# CTRL_LOGIC.net
KiCad netlist of a schematic drawn in Altium Designer
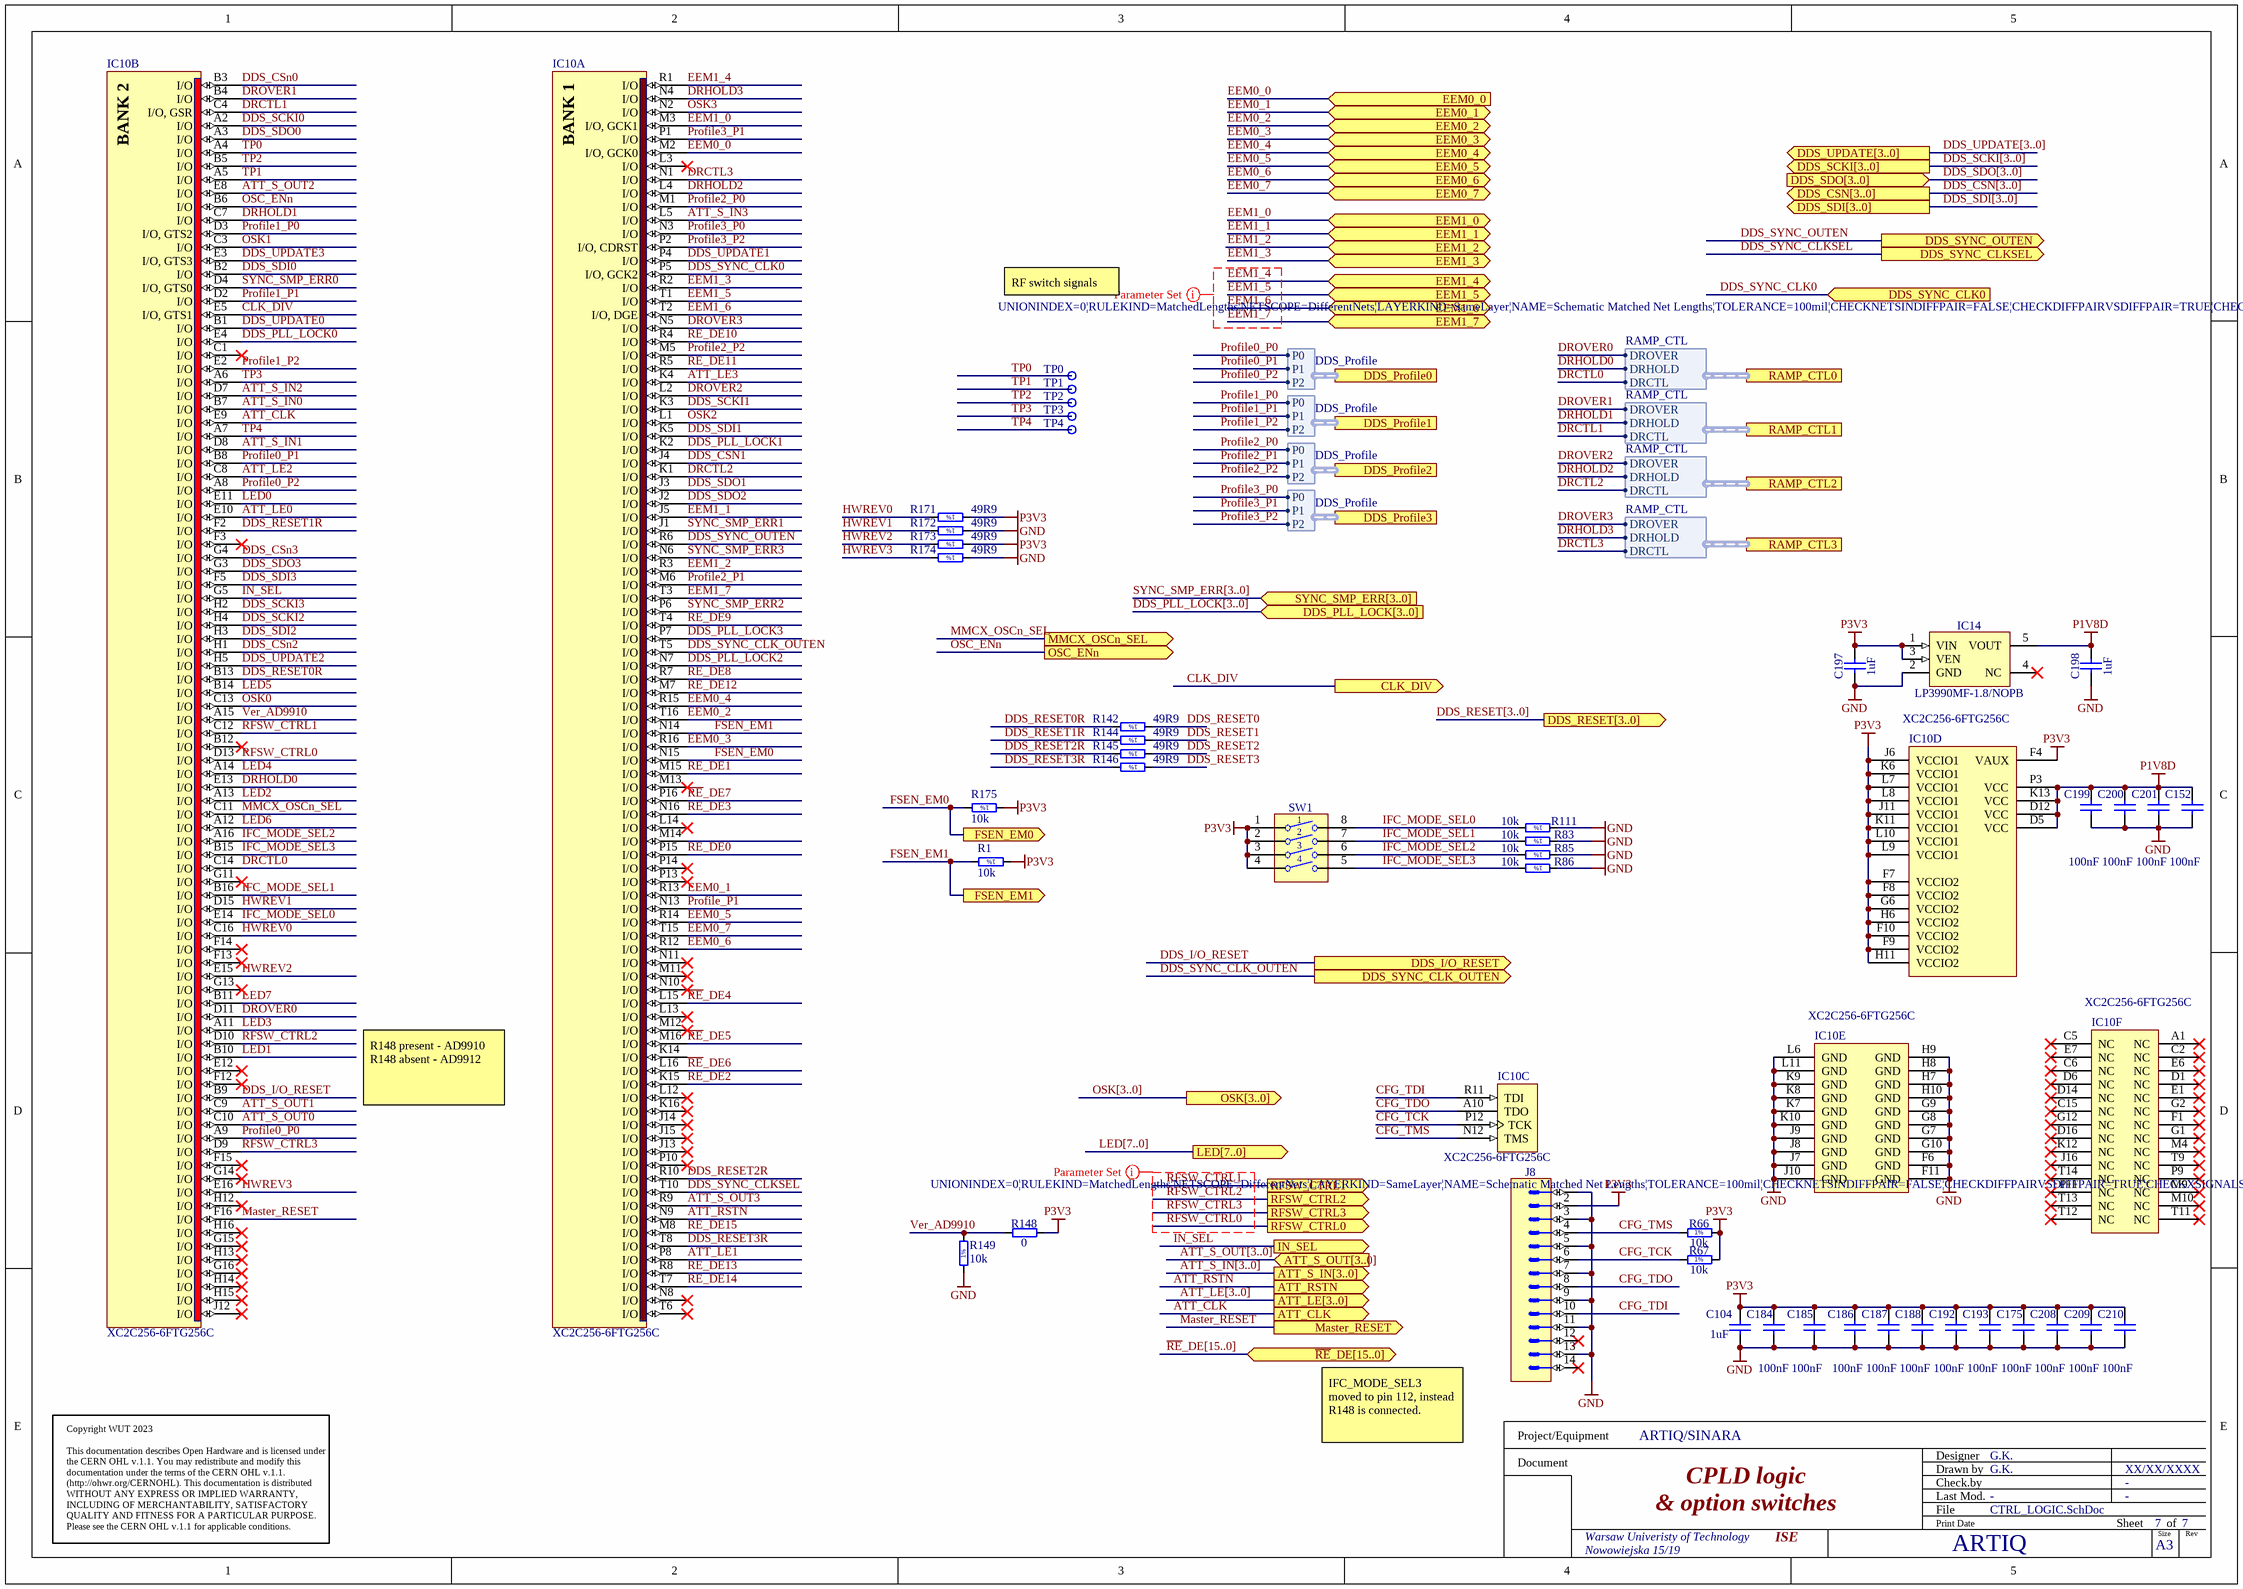
[diagram p0: CTRL_LOGIC.SchDoc]

(export (version "E")
  (design (tool "Eeschema 10.0.6"))
  (components
    (comp (ref "C104")
      (value "1uF")
      (footprint "CAPC1005X55N")
      (description "Non-polarised capacitor")
      (fields
        (field (name "PART NUMBER") "CC0402_1UF_16V_10%_X5R")
        (field (name "VOLTAGE") "16V")
        (field (name "AUTHOR") "CERN DEM JLC")
      )
      (libsource (lib "Capacitors") (part "Capacitor - non polarized"))
    )
    (comp (ref "C152")
      (value "100nF")
      (footprint "CAPC1005X55N")
      (description "Non-polarised capacitor")
      (fields
        (field (name "PART NUMBER") "CC0402_100NF_16V_10%_X5R")
        (field (name "VOLTAGE") "16V")
        (field (name "AUTHOR") "CERN DEM JLC")
      )
      (libsource (lib "Capacitors") (part "Capacitor - non polarized"))
    )
    (comp (ref "C175")
      (value "100nF")
      (footprint "CAPC1005X55N")
      (description "Non-polarised capacitor")
      (fields
        (field (name "PART NUMBER") "CC0402_100NF_16V_10%_X5R")
        (field (name "VOLTAGE") "16V")
        (field (name "AUTHOR") "CERN DEM JLC")
      )
      (libsource (lib "Capacitors") (part "Capacitor - non polarized"))
    )
    (comp (ref "C184")
      (value "100nF")
      (footprint "CAPC1005X55N")
      (description "Non-polarised capacitor")
      (fields
        (field (name "PART NUMBER") "CC0402_100NF_16V_10%_X5R")
        (field (name "VOLTAGE") "16V")
        (field (name "AUTHOR") "CERN DEM JLC")
      )
      (libsource (lib "Capacitors") (part "Capacitor - non polarized"))
    )
    (comp (ref "C185")
      (value "100nF")
      (footprint "CAPC1005X55N")
      (description "Non-polarised capacitor")
      (fields
        (field (name "PART NUMBER") "CC0402_100NF_16V_10%_X5R")
        (field (name "VOLTAGE") "16V")
        (field (name "AUTHOR") "CERN DEM JLC")
      )
      (libsource (lib "Capacitors") (part "Capacitor - non polarized"))
    )
    (comp (ref "C186")
      (value "100nF")
      (footprint "CAPC1005X55N")
      (description "Non-polarised capacitor")
      (fields
        (field (name "PART NUMBER") "CC0402_100NF_16V_10%_X5R")
        (field (name "VOLTAGE") "16V")
        (field (name "AUTHOR") "CERN DEM JLC")
      )
      (libsource (lib "Capacitors") (part "Capacitor - non polarized"))
    )
    (comp (ref "C187")
      (value "100nF")
      (footprint "CAPC1005X55N")
      (description "Non-polarised capacitor")
      (fields
        (field (name "PART NUMBER") "CC0402_100NF_16V_10%_X5R")
        (field (name "VOLTAGE") "16V")
        (field (name "AUTHOR") "CERN DEM JLC")
      )
      (libsource (lib "Capacitors") (part "Capacitor - non polarized"))
    )
    (comp (ref "C188")
      (value "100nF")
      (footprint "CAPC1005X55N")
      (description "Non-polarised capacitor")
      (fields
        (field (name "PART NUMBER") "CC0402_100NF_16V_10%_X5R")
        (field (name "VOLTAGE") "16V")
        (field (name "AUTHOR") "CERN DEM JLC")
      )
      (libsource (lib "Capacitors") (part "Capacitor - non polarized"))
    )
    (comp (ref "C192")
      (value "100nF")
      (footprint "CAPC1005X55N")
      (description "Non-polarised capacitor")
      (fields
        (field (name "PART NUMBER") "CC0402_100NF_16V_10%_X5R")
        (field (name "VOLTAGE") "16V")
        (field (name "AUTHOR") "CERN DEM JLC")
      )
      (libsource (lib "Capacitors") (part "Capacitor - non polarized"))
    )
    (comp (ref "C193")
      (value "100nF")
      (footprint "CAPC1005X55N")
      (description "Non-polarised capacitor")
      (fields
        (field (name "PART NUMBER") "CC0402_100NF_16V_10%_X5R")
        (field (name "VOLTAGE") "16V")
        (field (name "AUTHOR") "CERN DEM JLC")
      )
      (libsource (lib "Capacitors") (part "Capacitor - non polarized"))
    )
    (comp (ref "C197")
      (value "1uF")
      (footprint "CAPC1005X55N")
      (description "Non-polarised capacitor")
      (fields
        (field (name "PART NUMBER") "CC0402_1UF_16V_10%_X5R")
        (field (name "VOLTAGE") "16V")
        (field (name "AUTHOR") "CERN DEM JLC")
      )
      (libsource (lib "Capacitors") (part "Capacitor - non polarized"))
    )
    (comp (ref "C198")
      (value "1uF")
      (footprint "CAPC1005X55N")
      (description "Non-polarised capacitor")
      (fields
        (field (name "PART NUMBER") "CC0402_1UF_16V_10%_X5R")
        (field (name "VOLTAGE") "16V")
        (field (name "AUTHOR") "CERN DEM JLC")
      )
      (libsource (lib "Capacitors") (part "Capacitor - non polarized"))
    )
    (comp (ref "C199")
      (value "100nF")
      (footprint "CAPC1005X55N")
      (description "Non-polarised capacitor")
      (fields
        (field (name "PART NUMBER") "CC0402_100NF_16V_10%_X5R")
        (field (name "VOLTAGE") "16V")
        (field (name "AUTHOR") "CERN DEM JLC")
      )
      (libsource (lib "Capacitors") (part "Capacitor - non polarized"))
    )
    (comp (ref "C200")
      (value "100nF")
      (footprint "CAPC1005X55N")
      (description "Non-polarised capacitor")
      (fields
        (field (name "PART NUMBER") "CC0402_100NF_16V_10%_X5R")
        (field (name "VOLTAGE") "16V")
        (field (name "AUTHOR") "CERN DEM JLC")
      )
      (libsource (lib "Capacitors") (part "Capacitor - non polarized"))
    )
    (comp (ref "C201")
      (value "100nF")
      (footprint "CAPC1005X55N")
      (description "Non-polarised capacitor")
      (fields
        (field (name "PART NUMBER") "CC0402_100NF_16V_10%_X5R")
        (field (name "VOLTAGE") "16V")
        (field (name "AUTHOR") "CERN DEM JLC")
      )
      (libsource (lib "Capacitors") (part "Capacitor - non polarized"))
    )
    (comp (ref "C208")
      (value "100nF")
      (footprint "CAPC1005X55N")
      (description "Non-polarised capacitor")
      (fields
        (field (name "PART NUMBER") "CC0402_100NF_16V_10%_X5R")
        (field (name "VOLTAGE") "16V")
        (field (name "AUTHOR") "CERN DEM JLC")
      )
      (libsource (lib "Capacitors") (part "Capacitor - non polarized"))
    )
    (comp (ref "C209")
      (value "100nF")
      (footprint "CAPC1005X55N")
      (description "Non-polarised capacitor")
      (fields
        (field (name "PART NUMBER") "CC0402_100NF_16V_10%_X5R")
        (field (name "VOLTAGE") "16V")
        (field (name "AUTHOR") "CERN DEM JLC")
      )
      (libsource (lib "Capacitors") (part "Capacitor - non polarized"))
    )
    (comp (ref "C210")
      (value "100nF")
      (footprint "CAPC1005X55N")
      (description "Non-polarised capacitor")
      (fields
        (field (name "PART NUMBER") "CC0402_100NF_16V_10%_X5R")
        (field (name "VOLTAGE") "16V")
        (field (name "AUTHOR") "CERN DEM JLC")
      )
      (libsource (lib "Capacitors") (part "Capacitor - non polarized"))
    )
    (comp (ref "IC10")
      (value "XC2C256-6FTG256C")
      (footprint "FTG256")
      (description "CoolRunner-II 1.8V, 256 Macrocell CPLD, 184 User I/Os, 256-Ball FTBGA, Commercial Grade, Pb-Free")
      (libsource (lib "Altium Content Vault") (part "PLD-XCR-2C256-FT256"))
    )
    (comp (ref "IC14")
      (value "LP3990MF-1.8/NOPB")
      (footprint "SOT95P284X122-5N")
      (description "1.8V, 150mA Linear Voltage Regulator For Digital Applications")
      (fields (field (name "MANUFACTURER") "TEXAS INSTRUMENTS") (field (name "AUTHOR") "CERN DEM JLC"))
      (libsource (lib "ICs And Semiconductors") (part "LP3990MF"))
    )
    (comp (ref "J8")
      (value "Milli-Grid™")
      (footprint "MOLEX_87832-1420")
      (description "Connector 14 Male")
      (fields
        (field (name "PART NUMBER") "MOLEX_87832-1420")
        (field (name "MANUFACTURER") "MOLEX")
        (field (name "AUTHOR") "CERN DEM JLC")
      )
      (libsource (lib "Connectors") (part "Connector 14 Male"))
    )
    (comp (ref "R1")
      (value "10k")
      (footprint "RESC1005X40N")
      (description "Resistor - 1%")
      (fields
        (field (name "PART NUMBER") "R0402_10K_1%_0.0625W_100PPM")
        (field (name "POWER") "0.0625W")
        (field (name "AUTHOR") "CERN DEM JLC")
      )
      (libsource (lib "Resistors") (part "Resistor - 1%"))
    )
    (comp (ref "R66")
      (value "10k")
      (footprint "RESC1005X40N")
      (description "Resistor - 1%")
      (fields
        (field (name "PART NUMBER") "R0402_10K_1%_0.0625W_100PPM")
        (field (name "POWER") "0.0625W")
        (field (name "AUTHOR") "CERN DEM JLC")
      )
      (libsource (lib "Resistors") (part "Resistor - 1%"))
    )
    (comp (ref "R67")
      (value "10k")
      (footprint "RESC1005X40N")
      (description "Resistor - 1%")
      (fields
        (field (name "PART NUMBER") "R0402_10K_1%_0.0625W_100PPM")
        (field (name "POWER") "0.0625W")
        (field (name "AUTHOR") "CERN DEM JLC")
      )
      (libsource (lib "Resistors") (part "Resistor - 1%"))
    )
    (comp (ref "R83")
      (value "10k")
      (footprint "RESC1005X40N")
      (description "Resistor - 1%")
      (fields
        (field (name "PART NUMBER") "R0402_10K_1%_0.0625W_100PPM")
        (field (name "POWER") "0.0625W")
        (field (name "AUTHOR") "CERN DEM JLC")
      )
      (libsource (lib "Resistors") (part "Resistor - 1%"))
    )
    (comp (ref "R85")
      (value "10k")
      (footprint "RESC1005X40N")
      (description "Resistor - 1%")
      (fields
        (field (name "PART NUMBER") "R0402_10K_1%_0.0625W_100PPM")
        (field (name "POWER") "0.0625W")
        (field (name "AUTHOR") "CERN DEM JLC")
      )
      (libsource (lib "Resistors") (part "Resistor - 1%"))
    )
    (comp (ref "R86")
      (value "10k")
      (footprint "RESC1005X40N")
      (description "Resistor - 1%")
      (fields
        (field (name "PART NUMBER") "R0402_10K_1%_0.0625W_100PPM")
        (field (name "POWER") "0.0625W")
        (field (name "AUTHOR") "CERN DEM JLC")
      )
      (libsource (lib "Resistors") (part "Resistor - 1%"))
    )
    (comp (ref "R111")
      (value "10k")
      (footprint "RESC1005X40N")
      (description "Resistor - 1%")
      (fields
        (field (name "PART NUMBER") "R0402_10K_1%_0.0625W_100PPM")
        (field (name "POWER") "0.0625W")
        (field (name "AUTHOR") "CERN DEM JLC")
      )
      (libsource (lib "Resistors") (part "Resistor - 1%"))
    )
    (comp (ref "R142")
      (value "49R9")
      (footprint "RESC1005X40N")
      (description "Resistor - 1%")
      (fields
        (field (name "PART NUMBER") "R0402_49R9_1%_0.0625W_100PPM")
        (field (name "POWER") "0.0625W")
        (field (name "AUTHOR") "CERN DEM JLC")
      )
      (libsource (lib "Resistors") (part "Resistor - 1%"))
    )
    (comp (ref "R144")
      (value "49R9")
      (footprint "RESC1005X40N")
      (description "Resistor - 1%")
      (fields
        (field (name "PART NUMBER") "R0402_49R9_1%_0.0625W_100PPM")
        (field (name "POWER") "0.0625W")
        (field (name "AUTHOR") "CERN DEM JLC")
      )
      (libsource (lib "Resistors") (part "Resistor - 1%"))
    )
    (comp (ref "R145")
      (value "49R9")
      (footprint "RESC1005X40N")
      (description "Resistor - 1%")
      (fields
        (field (name "PART NUMBER") "R0402_49R9_1%_0.0625W_100PPM")
        (field (name "POWER") "0.0625W")
        (field (name "AUTHOR") "CERN DEM JLC")
      )
      (libsource (lib "Resistors") (part "Resistor - 1%"))
    )
    (comp (ref "R146")
      (value "49R9")
      (footprint "RESC1005X40N")
      (description "Resistor - 1%")
      (fields
        (field (name "PART NUMBER") "R0402_49R9_1%_0.0625W_100PPM")
        (field (name "POWER") "0.0625W")
        (field (name "AUTHOR") "CERN DEM JLC")
      )
      (libsource (lib "Resistors") (part "Resistor - 1%"))
    )
    (comp (ref "R148")
      (value "0")
      (footprint "RESC1005X40N")
      (description "Resistor")
      (fields
        (field (name "PART NUMBER") "R0402_0R_JUMPER")
        (field (name "MANUFACTURER") "GENERIC")
        (field (name "AUTHOR") "CERN DEM JLC")
      )
      (libsource (lib "Resistors") (part "Resistor"))
    )
    (comp (ref "R149")
      (value "10k")
      (footprint "RESC1005X40N")
      (description "Resistor - 1%")
      (fields
        (field (name "PART NUMBER") "R0402_10K_1%_0.0625W_100PPM")
        (field (name "POWER") "0.0625W")
        (field (name "AUTHOR") "CERN DEM JLC")
      )
      (libsource (lib "Resistors") (part "Resistor - 1%"))
    )
    (comp (ref "R171")
      (value "49R9")
      (footprint "RESC1005X40N")
      (description "Resistor - 1%")
      (fields
        (field (name "PART NUMBER") "R0402_49R9_1%_0.0625W_100PPM")
        (field (name "POWER") "0.0625W")
        (field (name "AUTHOR") "CERN DEM JLC")
      )
      (libsource (lib "Resistors") (part "Resistor - 1%"))
    )
    (comp (ref "R172")
      (value "49R9")
      (footprint "RESC1005X40N")
      (description "Resistor - 1%")
      (fields
        (field (name "PART NUMBER") "R0402_49R9_1%_0.0625W_100PPM")
        (field (name "POWER") "0.0625W")
        (field (name "AUTHOR") "CERN DEM JLC")
      )
      (libsource (lib "Resistors") (part "Resistor - 1%"))
    )
    (comp (ref "R173")
      (value "49R9")
      (footprint "RESC1005X40N")
      (description "Resistor - 1%")
      (fields
        (field (name "PART NUMBER") "R0402_49R9_1%_0.0625W_100PPM")
        (field (name "POWER") "0.0625W")
        (field (name "AUTHOR") "CERN DEM JLC")
      )
      (libsource (lib "Resistors") (part "Resistor - 1%"))
    )
    (comp (ref "R174")
      (value "49R9")
      (footprint "RESC1005X40N")
      (description "Resistor - 1%")
      (fields
        (field (name "PART NUMBER") "R0402_49R9_1%_0.0625W_100PPM")
        (field (name "POWER") "0.0625W")
        (field (name "AUTHOR") "CERN DEM JLC")
      )
      (libsource (lib "Resistors") (part "Resistor - 1%"))
    )
    (comp (ref "R175")
      (value "10k")
      (footprint "RESC1005X40N")
      (description "Resistor - 1%")
      (fields
        (field (name "PART NUMBER") "R0402_10K_1%_0.0625W_100PPM")
        (field (name "POWER") "0.0625W")
        (field (name "AUTHOR") "CERN DEM JLC")
      )
      (libsource (lib "Resistors") (part "Resistor - 1%"))
    )
    (comp (ref "SW1")
      (value "Switch")
      (footprint "SW_OMRON_A6S-4102-H")
      (description "4 Ways SPST DIP Switch")
      (fields
        (field (name "PART NUMBER") "SW_OMRON_A6S-4102-H")
        (field (name "MANUFACTURER") "OMRON")
        (field (name "AUTHOR") "CERN DEM JMW")
      )
      (libsource (lib "Eletro-mechanical") (part "SW 4x SPST DIP Switch"))
    )
    (comp (ref "TP0")
      (value "Test Point")
      (footprint "TPS127")
      (fields (field (name "PART NUMBER") "SMD_PAD_1.27X1.27MM") (field (name "AUTHOR") "CERN DEM JLC"))
      (libsource (lib "Eletro-mechanical") (part "Test Point"))
    )
    (comp (ref "TP1")
      (value "Test Point")
      (footprint "TPS127")
      (fields (field (name "PART NUMBER") "SMD_PAD_1.27X1.27MM") (field (name "AUTHOR") "CERN DEM JLC"))
      (libsource (lib "Eletro-mechanical") (part "Test Point"))
    )
    (comp (ref "TP2")
      (value "Test Point")
      (footprint "TPS127")
      (fields (field (name "PART NUMBER") "SMD_PAD_1.27X1.27MM") (field (name "AUTHOR") "CERN DEM JLC"))
      (libsource (lib "Eletro-mechanical") (part "Test Point"))
    )
    (comp (ref "TP3")
      (value "Test Point")
      (footprint "TPS127")
      (fields (field (name "PART NUMBER") "SMD_PAD_1.27X1.27MM") (field (name "AUTHOR") "CERN DEM JLC"))
      (libsource (lib "Eletro-mechanical") (part "Test Point"))
    )
    (comp (ref "TP4")
      (value "Test Point")
      (footprint "TPS127")
      (fields (field (name "PART NUMBER") "SMD_PAD_1.27X1.27MM") (field (name "AUTHOR") "CERN DEM JLC"))
      (libsource (lib "Eletro-mechanical") (part "Test Point"))
    )
  )
  (nets
    (net (code "6") (name "/ATT_CLK") (class "Default")
      (node (ref "IC10") (pin "E9") (pinfunction "I/O_E9") (pintype "bidirectional"))
    )
    (net (code "7") (name "/ATT_LE0") (class "Default")
      (node (ref "IC10") (pin "E10") (pinfunction "I/O_E10") (pintype "bidirectional"))
    )
    (net (code "8") (name "/ATT_LE1") (class "Default")
      (node (ref "IC10") (pin "P8") (pinfunction "I/O_P8") (pintype "bidirectional"))
    )
    (net (code "9") (name "/ATT_LE2") (class "Default")
      (node (ref "IC10") (pin "C8") (pinfunction "I/O_C8") (pintype "bidirectional"))
    )
    (net (code "10") (name "/ATT_LE3") (class "Default")
      (node (ref "IC10") (pin "K4") (pinfunction "I/O_K4") (pintype "bidirectional"))
    )
    (net (code "12") (name "/ATT_RSTN") (class "Default")
      (node (ref "IC10") (pin "N9") (pinfunction "I/O_N9") (pintype "bidirectional"))
    )
    (net (code "13") (name "/ATT_S_IN0") (class "Default")
      (node (ref "IC10") (pin "B7") (pinfunction "I/O_B7") (pintype "bidirectional"))
    )
    (net (code "14") (name "/ATT_S_IN1") (class "Default")
      (node (ref "IC10") (pin "D8") (pinfunction "I/O_D8") (pintype "bidirectional"))
    )
    (net (code "15") (name "/ATT_S_IN2") (class "Default")
      (node (ref "IC10") (pin "D7") (pinfunction "I/O_D7") (pintype "bidirectional"))
    )
    (net (code "16") (name "/ATT_S_IN3") (class "Default")
      (node (ref "IC10") (pin "L5") (pinfunction "I/O_L5") (pintype "bidirectional"))
    )
    (net (code "18") (name "/ATT_S_OUT0") (class "Default")
      (node (ref "IC10") (pin "C10") (pinfunction "I/O_C10") (pintype "bidirectional"))
    )
    (net (code "19") (name "/ATT_S_OUT1") (class "Default")
      (node (ref "IC10") (pin "C9") (pinfunction "I/O_C9") (pintype "bidirectional"))
    )
    (net (code "20") (name "/ATT_S_OUT2") (class "Default")
      (node (ref "IC10") (pin "E8") (pinfunction "I/O_E8") (pintype "bidirectional"))
    )
    (net (code "21") (name "/ATT_S_OUT3") (class "Default")
      (node (ref "IC10") (pin "R9") (pinfunction "I/O_R9") (pintype "bidirectional"))
    )
    (net (code "23") (name "/CFG_TCK") (class "Default")
      (node (ref "IC10") (pin "P12") (pinfunction "TCK_P12") (pintype "input"))
      (node (ref "J8") (pin "6") (pinfunction "6_6") (pintype "bidirectional"))
      (node (ref "R67") (pin "1") (pinfunction "1_1") (pintype "passive"))
    )
    (net (code "24") (name "/CFG_TDI") (class "Default")
      (node (ref "IC10") (pin "R11") (pinfunction "TDI_R11") (pintype "input"))
      (node (ref "J8") (pin "10") (pinfunction "10_10") (pintype "bidirectional"))
    )
    (net (code "25") (name "/CFG_TDO") (class "Default")
      (node (ref "IC10") (pin "A10") (pinfunction "TDO_A10") (pintype "passive"))
      (node (ref "J8") (pin "8") (pinfunction "8_8") (pintype "bidirectional"))
    )
    (net (code "26") (name "/CFG_TMS") (class "Default")
      (node (ref "IC10") (pin "N12") (pinfunction "TMS_N12") (pintype "input"))
      (node (ref "J8") (pin "4") (pinfunction "4_4") (pintype "bidirectional"))
      (node (ref "R66") (pin "1") (pinfunction "1_1") (pintype "passive"))
    )
    (net (code "27") (name "/CLK_DIV") (class "Default")
      (node (ref "IC10") (pin "E5") (pinfunction "I/O,_GTS1_E5") (pintype "bidirectional"))
    )
    (net (code "28") (name "/DDS_CSN1") (class "Default")
      (node (ref "IC10") (pin "J4") (pinfunction "I/O_J4") (pintype "bidirectional"))
    )
    (net (code "30") (name "/DDS_CSn0") (class "Default")
      (node (ref "IC10") (pin "B3") (pinfunction "I/O_B3") (pintype "bidirectional"))
    )
    (net (code "31") (name "/DDS_CSn2") (class "Default")
      (node (ref "IC10") (pin "H1") (pinfunction "I/O_H1") (pintype "bidirectional"))
    )
    (net (code "32") (name "/DDS_CSn3") (class "Default")
      (node (ref "IC10") (pin "G4") (pinfunction "I/O_G4") (pintype "bidirectional"))
    )
    (net (code "33") (name "/DDS_I{slash}O_RESET") (class "Default")
      (node (ref "IC10") (pin "B9") (pinfunction "I/O_B9") (pintype "bidirectional"))
    )
    (net (code "34") (name "/DDS_PLL_LOCK0") (class "Default")
      (node (ref "IC10") (pin "E4") (pinfunction "I/O_E4") (pintype "bidirectional"))
    )
    (net (code "35") (name "/DDS_PLL_LOCK1") (class "Default")
      (node (ref "IC10") (pin "K2") (pinfunction "I/O_K2") (pintype "bidirectional"))
    )
    (net (code "36") (name "/DDS_PLL_LOCK2") (class "Default")
      (node (ref "IC10") (pin "N7") (pinfunction "I/O_N7") (pintype "bidirectional"))
    )
    (net (code "37") (name "/DDS_PLL_LOCK3") (class "Default")
      (node (ref "IC10") (pin "P7") (pinfunction "I/O_P7") (pintype "bidirectional"))
    )
    (net (code "39") (name "/DDS_RESET0") (class "Default")
      (node (ref "R142") (pin "1") (pinfunction "1_1") (pintype "passive"))
    )
    (net (code "40") (name "/DDS_RESET0R") (class "Default")
      (node (ref "IC10") (pin "B13") (pinfunction "I/O_B13") (pintype "bidirectional"))
      (node (ref "R142") (pin "2") (pinfunction "2_2") (pintype "passive"))
    )
    (net (code "41") (name "/DDS_RESET1") (class "Default")
      (node (ref "R144") (pin "1") (pinfunction "1_1") (pintype "passive"))
    )
    (net (code "42") (name "/DDS_RESET1R") (class "Default")
      (node (ref "IC10") (pin "F2") (pinfunction "I/O_F2") (pintype "bidirectional"))
      (node (ref "R144") (pin "2") (pinfunction "2_2") (pintype "passive"))
    )
    (net (code "43") (name "/DDS_RESET2") (class "Default")
      (node (ref "R145") (pin "1") (pinfunction "1_1") (pintype "passive"))
    )
    (net (code "44") (name "/DDS_RESET2R") (class "Default")
      (node (ref "IC10") (pin "R10") (pinfunction "I/O_R10") (pintype "bidirectional"))
      (node (ref "R145") (pin "2") (pinfunction "2_2") (pintype "passive"))
    )
    (net (code "45") (name "/DDS_RESET3") (class "Default")
      (node (ref "R146") (pin "1") (pinfunction "1_1") (pintype "passive"))
    )
    (net (code "46") (name "/DDS_RESET3R") (class "Default")
      (node (ref "IC10") (pin "T8") (pinfunction "I/O_T8") (pintype "bidirectional"))
      (node (ref "R146") (pin "2") (pinfunction "2_2") (pintype "passive"))
    )
    (net (code "48") (name "/DDS_SCKI0") (class "Default")
      (node (ref "IC10") (pin "A2") (pinfunction "I/O_A2") (pintype "bidirectional"))
    )
    (net (code "49") (name "/DDS_SCKI1") (class "Default")
      (node (ref "IC10") (pin "K3") (pinfunction "I/O_K3") (pintype "bidirectional"))
    )
    (net (code "50") (name "/DDS_SCKI2") (class "Default")
      (node (ref "IC10") (pin "H4") (pinfunction "I/O_H4") (pintype "bidirectional"))
    )
    (net (code "51") (name "/DDS_SCKI3") (class "Default")
      (node (ref "IC10") (pin "H2") (pinfunction "I/O_H2") (pintype "bidirectional"))
    )
    (net (code "53") (name "/DDS_SDI0") (class "Default")
      (node (ref "IC10") (pin "B2") (pinfunction "I/O_B2") (pintype "bidirectional"))
    )
    (net (code "54") (name "/DDS_SDI1") (class "Default")
      (node (ref "IC10") (pin "K5") (pinfunction "I/O_K5") (pintype "bidirectional"))
    )
    (net (code "55") (name "/DDS_SDI2") (class "Default")
      (node (ref "IC10") (pin "H3") (pinfunction "I/O_H3") (pintype "bidirectional"))
    )
    (net (code "56") (name "/DDS_SDI3") (class "Default")
      (node (ref "IC10") (pin "F5") (pinfunction "I/O_F5") (pintype "bidirectional"))
    )
    (net (code "58") (name "/DDS_SDO0") (class "Default")
      (node (ref "IC10") (pin "A3") (pinfunction "I/O_A3") (pintype "bidirectional"))
    )
    (net (code "59") (name "/DDS_SDO1") (class "Default")
      (node (ref "IC10") (pin "J3") (pinfunction "I/O_J3") (pintype "bidirectional"))
    )
    (net (code "60") (name "/DDS_SDO2") (class "Default")
      (node (ref "IC10") (pin "J2") (pinfunction "I/O_J2") (pintype "bidirectional"))
    )
    (net (code "61") (name "/DDS_SDO3") (class "Default")
      (node (ref "IC10") (pin "G3") (pinfunction "I/O_G3") (pintype "bidirectional"))
    )
    (net (code "63") (name "/DDS_SYNC_CLK0") (class "Default")
      (node (ref "IC10") (pin "P5") (pinfunction "I/O,_GCK2_P5") (pintype "bidirectional"))
    )
    (net (code "64") (name "/DDS_SYNC_CLKSEL") (class "Default")
      (node (ref "IC10") (pin "T10") (pinfunction "I/O_T10") (pintype "bidirectional"))
    )
    (net (code "65") (name "/DDS_SYNC_CLK_OUTEN") (class "Default")
      (node (ref "IC10") (pin "T5") (pinfunction "I/O_T5") (pintype "bidirectional"))
    )
    (net (code "66") (name "/DDS_SYNC_OUTEN") (class "Default")
      (node (ref "IC10") (pin "R6") (pinfunction "I/O_R6") (pintype "bidirectional"))
    )
    (net (code "67") (name "/DDS_UPDATE0") (class "Default")
      (node (ref "IC10") (pin "B1") (pinfunction "I/O_B1") (pintype "bidirectional"))
    )
    (net (code "68") (name "/DDS_UPDATE1") (class "Default")
      (node (ref "IC10") (pin "P4") (pinfunction "I/O_P4") (pintype "bidirectional"))
    )
    (net (code "69") (name "/DDS_UPDATE2") (class "Default")
      (node (ref "IC10") (pin "H5") (pinfunction "I/O_H5") (pintype "bidirectional"))
    )
    (net (code "70") (name "/DDS_UPDATE3") (class "Default")
      (node (ref "IC10") (pin "E3") (pinfunction "I/O,_GTS3_E3") (pintype "bidirectional"))
    )
    (net (code "72") (name "/DRCTL0") (class "Default")
      (node (ref "IC10") (pin "C14") (pinfunction "I/O_C14") (pintype "bidirectional"))
    )
    (net (code "73") (name "/DRCTL1") (class "Default")
      (node (ref "IC10") (pin "C4") (pinfunction "I/O,_GSR_C4") (pintype "bidirectional"))
    )
    (net (code "74") (name "/DRCTL2") (class "Default")
      (node (ref "IC10") (pin "K1") (pinfunction "I/O_K1") (pintype "bidirectional"))
    )
    (net (code "75") (name "/DRCTL3") (class "Default")
      (node (ref "IC10") (pin "N1") (pinfunction "I/O_N1") (pintype "bidirectional"))
    )
    (net (code "76") (name "/DRHOLD0") (class "Default")
      (node (ref "IC10") (pin "E13") (pinfunction "I/O_E13") (pintype "bidirectional"))
    )
    (net (code "77") (name "/DRHOLD1") (class "Default")
      (node (ref "IC10") (pin "C7") (pinfunction "I/O_C7") (pintype "bidirectional"))
    )
    (net (code "78") (name "/DRHOLD2") (class "Default")
      (node (ref "IC10") (pin "L4") (pinfunction "I/O_L4") (pintype "bidirectional"))
    )
    (net (code "79") (name "/DRHOLD3") (class "Default")
      (node (ref "IC10") (pin "N4") (pinfunction "I/O_N4") (pintype "bidirectional"))
    )
    (net (code "80") (name "/DROVER0") (class "Default")
      (node (ref "IC10") (pin "D11") (pinfunction "I/O_D11") (pintype "bidirectional"))
    )
    (net (code "81") (name "/DROVER1") (class "Default")
      (node (ref "IC10") (pin "B4") (pinfunction "I/O_B4") (pintype "bidirectional"))
    )
    (net (code "82") (name "/DROVER2") (class "Default")
      (node (ref "IC10") (pin "L2") (pinfunction "I/O_L2") (pintype "bidirectional"))
    )
    (net (code "83") (name "/DROVER3") (class "Default")
      (node (ref "IC10") (pin "N5") (pinfunction "I/O_N5") (pintype "bidirectional"))
    )
    (net (code "84") (name "/EEM0_0") (class "Default")
      (node (ref "IC10") (pin "M2") (pinfunction "I/O,_GCK0_M2") (pintype "bidirectional"))
    )
    (net (code "85") (name "/EEM0_1") (class "Default")
      (node (ref "IC10") (pin "R13") (pinfunction "I/O_R13") (pintype "bidirectional"))
    )
    (net (code "86") (name "/EEM0_2") (class "Default")
      (node (ref "IC10") (pin "T16") (pinfunction "I/O_T16") (pintype "bidirectional"))
    )
    (net (code "87") (name "/EEM0_3") (class "Default")
      (node (ref "IC10") (pin "R16") (pinfunction "I/O_R16") (pintype "bidirectional"))
    )
    (net (code "88") (name "/EEM0_4") (class "Default")
      (node (ref "IC10") (pin "R15") (pinfunction "I/O_R15") (pintype "bidirectional"))
    )
    (net (code "89") (name "/EEM0_5") (class "Default")
      (node (ref "IC10") (pin "R14") (pinfunction "I/O_R14") (pintype "bidirectional"))
    )
    (net (code "90") (name "/EEM0_6") (class "Default")
      (node (ref "IC10") (pin "R12") (pinfunction "I/O_R12") (pintype "bidirectional"))
    )
    (net (code "91") (name "/EEM0_7") (class "Default")
      (node (ref "IC10") (pin "T15") (pinfunction "I/O_T15") (pintype "bidirectional"))
    )
    (net (code "92") (name "/EEM1_0") (class "Default")
      (node (ref "IC10") (pin "M3") (pinfunction "I/O,_GCK1_M3") (pintype "bidirectional"))
    )
    (net (code "93") (name "/EEM1_1") (class "Default")
      (node (ref "IC10") (pin "J5") (pinfunction "I/O_J5") (pintype "bidirectional"))
    )
    (net (code "94") (name "/EEM1_2") (class "Default")
      (node (ref "IC10") (pin "R3") (pinfunction "I/O_R3") (pintype "bidirectional"))
    )
    (net (code "95") (name "/EEM1_3") (class "Default")
      (node (ref "IC10") (pin "R2") (pinfunction "I/O_R2") (pintype "bidirectional"))
    )
    (net (code "96") (name "/EEM1_4") (class "Default")
      (node (ref "IC10") (pin "R1") (pinfunction "I/O_R1") (pintype "bidirectional"))
    )
    (net (code "97") (name "/EEM1_5") (class "Default")
      (node (ref "IC10") (pin "T1") (pinfunction "I/O_T1") (pintype "bidirectional"))
    )
    (net (code "98") (name "/EEM1_6") (class "Default")
      (node (ref "IC10") (pin "T2") (pinfunction "I/O,_DGE_T2") (pintype "bidirectional"))
    )
    (net (code "99") (name "/EEM1_7") (class "Default")
      (node (ref "IC10") (pin "T3") (pinfunction "I/O_T3") (pintype "bidirectional"))
    )
    (net (code "100") (name "/FSEN_EM0") (class "Default")
      (node (ref "IC10") (pin "N15") (pinfunction "I/O_N15") (pintype "bidirectional"))
      (node (ref "R175") (pin "2") (pinfunction "2_2") (pintype "passive"))
    )
    (net (code "101") (name "/FSEN_EM1") (class "Default")
      (node (ref "IC10") (pin "N14") (pinfunction "I/O_N14") (pintype "bidirectional"))
      (node (ref "R1") (pin "2") (pinfunction "2_2") (pintype "passive"))
    )
    (net (code "102") (name "/HWREV0") (class "Default")
      (node (ref "IC10") (pin "C16") (pinfunction "I/O_C16") (pintype "bidirectional"))
      (node (ref "R171") (pin "2") (pinfunction "2_2") (pintype "passive"))
    )
    (net (code "103") (name "/HWREV1") (class "Default")
      (node (ref "IC10") (pin "D15") (pinfunction "I/O_D15") (pintype "bidirectional"))
      (node (ref "R172") (pin "2") (pinfunction "2_2") (pintype "passive"))
    )
    (net (code "104") (name "/HWREV2") (class "Default")
      (node (ref "IC10") (pin "E15") (pinfunction "I/O_E15") (pintype "bidirectional"))
      (node (ref "R173") (pin "2") (pinfunction "2_2") (pintype "passive"))
    )
    (net (code "105") (name "/HWREV3") (class "Default")
      (node (ref "IC10") (pin "E16") (pinfunction "I/O_E16") (pintype "bidirectional"))
      (node (ref "R174") (pin "2") (pinfunction "2_2") (pintype "passive"))
    )
    (net (code "106") (name "/IFC_MODE_SEL0") (class "Default")
      (node (ref "IC10") (pin "E14") (pinfunction "I/O_E14") (pintype "bidirectional"))
      (node (ref "R111") (pin "2") (pinfunction "2_2") (pintype "passive"))
      (node (ref "SW1") (pin "8") (pinfunction "8_8") (pintype "passive"))
    )
    (net (code "107") (name "/IFC_MODE_SEL1") (class "Default")
      (node (ref "IC10") (pin "B16") (pinfunction "I/O_B16") (pintype "bidirectional"))
      (node (ref "R83") (pin "2") (pinfunction "2_2") (pintype "passive"))
      (node (ref "SW1") (pin "7") (pinfunction "7_7") (pintype "passive"))
    )
    (net (code "108") (name "/IFC_MODE_SEL2") (class "Default")
      (node (ref "IC10") (pin "A16") (pinfunction "I/O_A16") (pintype "bidirectional"))
      (node (ref "R85") (pin "2") (pinfunction "2_2") (pintype "passive"))
      (node (ref "SW1") (pin "6") (pinfunction "6_6") (pintype "passive"))
    )
    (net (code "109") (name "/IFC_MODE_SEL3") (class "Default")
      (node (ref "IC10") (pin "B15") (pinfunction "I/O_B15") (pintype "bidirectional"))
      (node (ref "R86") (pin "2") (pinfunction "2_2") (pintype "passive"))
      (node (ref "SW1") (pin "5") (pinfunction "5_5") (pintype "passive"))
    )
    (net (code "110") (name "/IN_SEL") (class "Default")
      (node (ref "IC10") (pin "G5") (pinfunction "I/O_G5") (pintype "bidirectional"))
    )
    (net (code "111") (name "/LED0") (class "Default")
      (node (ref "IC10") (pin "E11") (pinfunction "I/O_E11") (pintype "bidirectional"))
    )
    (net (code "112") (name "/LED1") (class "Default")
      (node (ref "IC10") (pin "B10") (pinfunction "I/O_B10") (pintype "bidirectional"))
    )
    (net (code "113") (name "/LED2") (class "Default")
      (node (ref "IC10") (pin "A13") (pinfunction "I/O_A13") (pintype "bidirectional"))
    )
    (net (code "114") (name "/LED3") (class "Default")
      (node (ref "IC10") (pin "A11") (pinfunction "I/O_A11") (pintype "bidirectional"))
    )
    (net (code "115") (name "/LED4") (class "Default")
      (node (ref "IC10") (pin "A14") (pinfunction "I/O_A14") (pintype "bidirectional"))
    )
    (net (code "116") (name "/LED5") (class "Default")
      (node (ref "IC10") (pin "B14") (pinfunction "I/O_B14") (pintype "bidirectional"))
    )
    (net (code "117") (name "/LED6") (class "Default")
      (node (ref "IC10") (pin "A12") (pinfunction "I/O_A12") (pintype "bidirectional"))
    )
    (net (code "118") (name "/LED7") (class "Default")
      (node (ref "IC10") (pin "B11") (pinfunction "I/O_B11") (pintype "bidirectional"))
    )
    (net (code "120") (name "/MMCX_OSCn_SEL") (class "Default")
      (node (ref "IC10") (pin "C11") (pinfunction "I/O_C11") (pintype "bidirectional"))
    )
    (net (code "121") (name "/Master_RESET") (class "Default")
      (node (ref "IC10") (pin "F16") (pinfunction "I/O_F16") (pintype "bidirectional"))
    )
    (net (code "122") (name "/OSC_ENn") (class "Default")
      (node (ref "IC10") (pin "B6") (pinfunction "I/O_B6") (pintype "bidirectional"))
    )
    (net (code "123") (name "/OSK0") (class "Default")
      (node (ref "IC10") (pin "C13") (pinfunction "I/O_C13") (pintype "bidirectional"))
    )
    (net (code "124") (name "/OSK1") (class "Default")
      (node (ref "IC10") (pin "C3") (pinfunction "I/O_C3") (pintype "bidirectional"))
    )
    (net (code "125") (name "/OSK2") (class "Default")
      (node (ref "IC10") (pin "L1") (pinfunction "I/O_L1") (pintype "bidirectional"))
    )
    (net (code "126") (name "/OSK3") (class "Default")
      (node (ref "IC10") (pin "N2") (pinfunction "I/O_N2") (pintype "bidirectional"))
    )
    (net (code "128") (name "/Profile0_P0") (class "Default")
      (node (ref "IC10") (pin "A9") (pinfunction "I/O_A9") (pintype "bidirectional"))
    )
    (net (code "129") (name "/Profile0_P1") (class "Default")
      (node (ref "IC10") (pin "B8") (pinfunction "I/O_B8") (pintype "bidirectional"))
    )
    (net (code "130") (name "/Profile0_P2") (class "Default")
      (node (ref "IC10") (pin "A8") (pinfunction "I/O_A8") (pintype "bidirectional"))
    )
    (net (code "131") (name "/Profile1_P0") (class "Default")
      (node (ref "IC10") (pin "D3") (pinfunction "I/O,_GTS2_D3") (pintype "bidirectional"))
    )
    (net (code "132") (name "/Profile1_P1") (class "Default")
      (node (ref "IC10") (pin "D2") (pinfunction "I/O_D2") (pintype "bidirectional"))
    )
    (net (code "133") (name "/Profile1_P2") (class "Default")
      (node (ref "IC10") (pin "E2") (pinfunction "I/O_E2") (pintype "bidirectional"))
    )
    (net (code "134") (name "/Profile2_P0") (class "Default")
      (node (ref "IC10") (pin "M1") (pinfunction "I/O_M1") (pintype "bidirectional"))
    )
    (net (code "135") (name "/Profile2_P1") (class "Default")
      (node (ref "IC10") (pin "M6") (pinfunction "I/O_M6") (pintype "bidirectional"))
    )
    (net (code "136") (name "/Profile2_P2") (class "Default")
      (node (ref "IC10") (pin "M5") (pinfunction "I/O_M5") (pintype "bidirectional"))
    )
    (net (code "137") (name "/Profile3_P0") (class "Default")
      (node (ref "IC10") (pin "N3") (pinfunction "I/O_N3") (pintype "bidirectional"))
    )
    (net (code "138") (name "/Profile3_P1") (class "Default")
      (node (ref "IC10") (pin "P1") (pinfunction "I/O_P1") (pintype "bidirectional"))
    )
    (net (code "139") (name "/Profile3_P2") (class "Default")
      (node (ref "IC10") (pin "P2") (pinfunction "I/O,_CDRST_P2") (pintype "bidirectional"))
    )
    (net (code "140") (name "/Profile_P1") (class "Default")
      (node (ref "IC10") (pin "N13") (pinfunction "I/O_N13") (pintype "bidirectional"))
    )
    (net (code "141") (name "/RFSW_CTRL0") (class "Default")
      (node (ref "IC10") (pin "D13") (pinfunction "I/O_D13") (pintype "bidirectional"))
    )
    (net (code "142") (name "/RFSW_CTRL1") (class "Default")
      (node (ref "IC10") (pin "C12") (pinfunction "I/O_C12") (pintype "bidirectional"))
    )
    (net (code "143") (name "/RFSW_CTRL2") (class "Default")
      (node (ref "IC10") (pin "D10") (pinfunction "I/O_D10") (pintype "bidirectional"))
    )
    (net (code "144") (name "/RFSW_CTRL3") (class "Default")
      (node (ref "IC10") (pin "D9") (pinfunction "I/O_D9") (pintype "bidirectional"))
    )
    (net (code "145") (name "/SYNC_SMP_ERR0") (class "Default")
      (node (ref "IC10") (pin "D4") (pinfunction "I/O,_GTS0_D4") (pintype "bidirectional"))
    )
    (net (code "146") (name "/SYNC_SMP_ERR1") (class "Default")
      (node (ref "IC10") (pin "J1") (pinfunction "I/O_J1") (pintype "bidirectional"))
    )
    (net (code "147") (name "/SYNC_SMP_ERR2") (class "Default")
      (node (ref "IC10") (pin "P6") (pinfunction "I/O_P6") (pintype "bidirectional"))
    )
    (net (code "148") (name "/SYNC_SMP_ERR3") (class "Default")
      (node (ref "IC10") (pin "N6") (pinfunction "I/O_N6") (pintype "bidirectional"))
    )
    (net (code "150") (name "/TP0") (class "Default")
      (node (ref "IC10") (pin "A4") (pinfunction "I/O_A4") (pintype "bidirectional"))
      (node (ref "TP0") (pin "1") (pinfunction "1_1") (pintype "bidirectional"))
    )
    (net (code "151") (name "/TP1") (class "Default")
      (node (ref "IC10") (pin "A5") (pinfunction "I/O_A5") (pintype "bidirectional"))
      (node (ref "TP1") (pin "1") (pinfunction "1_1") (pintype "bidirectional"))
    )
    (net (code "152") (name "/TP2") (class "Default")
      (node (ref "IC10") (pin "B5") (pinfunction "I/O_B5") (pintype "bidirectional"))
      (node (ref "TP2") (pin "1") (pinfunction "1_1") (pintype "bidirectional"))
    )
    (net (code "153") (name "/TP3") (class "Default")
      (node (ref "IC10") (pin "A6") (pinfunction "I/O_A6") (pintype "bidirectional"))
      (node (ref "TP3") (pin "1") (pinfunction "1_1") (pintype "bidirectional"))
    )
    (net (code "154") (name "/TP4") (class "Default")
      (node (ref "IC10") (pin "A7") (pinfunction "I/O_A7") (pintype "bidirectional"))
      (node (ref "TP4") (pin "1") (pinfunction "1_1") (pintype "bidirectional"))
    )
    (net (code "155") (name "/Ver_AD9910") (class "Default")
      (node (ref "IC10") (pin "A15") (pinfunction "I/O_A15") (pintype "bidirectional"))
      (node (ref "R148") (pin "1") (pinfunction "1_1") (pintype "passive"))
      (node (ref "R149") (pin "2") (pinfunction "2_2") (pintype "passive"))
    )
    (net (code "158") (name "/~{RE}_DE0") (class "Default")
      (node (ref "IC10") (pin "P15") (pinfunction "I/O_P15") (pintype "bidirectional"))
    )
    (net (code "159") (name "/~{RE}_DE1") (class "Default")
      (node (ref "IC10") (pin "M15") (pinfunction "I/O_M15") (pintype "bidirectional"))
    )
    (net (code "160") (name "/~{RE}_DE2") (class "Default")
      (node (ref "IC10") (pin "K15") (pinfunction "I/O_K15") (pintype "bidirectional"))
    )
    (net (code "161") (name "/~{RE}_DE3") (class "Default")
      (node (ref "IC10") (pin "N16") (pinfunction "I/O_N16") (pintype "bidirectional"))
    )
    (net (code "162") (name "/~{RE}_DE4") (class "Default")
      (node (ref "IC10") (pin "L15") (pinfunction "I/O_L15") (pintype "bidirectional"))
    )
    (net (code "163") (name "/~{RE}_DE5") (class "Default")
      (node (ref "IC10") (pin "M16") (pinfunction "I/O_M16") (pintype "bidirectional"))
    )
    (net (code "164") (name "/~{RE}_DE6") (class "Default")
      (node (ref "IC10") (pin "L16") (pinfunction "I/O_L16") (pintype "bidirectional"))
    )
    (net (code "165") (name "/~{RE}_DE7") (class "Default")
      (node (ref "IC10") (pin "P16") (pinfunction "I/O_P16") (pintype "bidirectional"))
    )
    (net (code "166") (name "/~{RE}_DE8") (class "Default")
      (node (ref "IC10") (pin "R7") (pinfunction "I/O_R7") (pintype "bidirectional"))
    )
    (net (code "167") (name "/~{RE}_DE9") (class "Default")
      (node (ref "IC10") (pin "T4") (pinfunction "I/O_T4") (pintype "bidirectional"))
    )
    (net (code "168") (name "/~{RE}_DE10") (class "Default")
      (node (ref "IC10") (pin "R4") (pinfunction "I/O_R4") (pintype "bidirectional"))
    )
    (net (code "169") (name "/~{RE}_DE11") (class "Default")
      (node (ref "IC10") (pin "R5") (pinfunction "I/O_R5") (pintype "bidirectional"))
    )
    (net (code "170") (name "/~{RE}_DE12") (class "Default")
      (node (ref "IC10") (pin "M7") (pinfunction "I/O_M7") (pintype "bidirectional"))
    )
    (net (code "171") (name "/~{RE}_DE13") (class "Default")
      (node (ref "IC10") (pin "R8") (pinfunction "I/O_R8") (pintype "bidirectional"))
    )
    (net (code "172") (name "/~{RE}_DE14") (class "Default")
      (node (ref "IC10") (pin "T7") (pinfunction "I/O_T7") (pintype "bidirectional"))
    )
    (net (code "173") (name "/~{RE}_DE15") (class "Default")
      (node (ref "IC10") (pin "M8") (pinfunction "I/O_M8") (pintype "bidirectional"))
    )
    (net (code "175") (name "GND") (class "Default")
      (node (ref "C104") (pin "1") (pinfunction "1_1") (pintype "passive"))
      (node (ref "C152") (pin "1") (pinfunction "1_1") (pintype "passive"))
      (node (ref "C175") (pin "1") (pinfunction "1_1") (pintype "passive"))
      (node (ref "C184") (pin "1") (pinfunction "1_1") (pintype "passive"))
      (node (ref "C185") (pin "1") (pinfunction "1_1") (pintype "passive"))
      (node (ref "C186") (pin "1") (pinfunction "1_1") (pintype "passive"))
      (node (ref "C187") (pin "1") (pinfunction "1_1") (pintype "passive"))
      (node (ref "C188") (pin "1") (pinfunction "1_1") (pintype "passive"))
      (node (ref "C192") (pin "1") (pinfunction "1_1") (pintype "passive"))
      (node (ref "C193") (pin "1") (pinfunction "1_1") (pintype "passive"))
      (node (ref "C197") (pin "1") (pinfunction "1_1") (pintype "passive"))
      (node (ref "C198") (pin "1") (pinfunction "1_1") (pintype "passive"))
      (node (ref "C199") (pin "1") (pinfunction "1_1") (pintype "passive"))
      (node (ref "C200") (pin "1") (pinfunction "1_1") (pintype "passive"))
      (node (ref "C201") (pin "1") (pinfunction "1_1") (pintype "passive"))
      (node (ref "C208") (pin "1") (pinfunction "1_1") (pintype "passive"))
      (node (ref "C209") (pin "1") (pinfunction "1_1") (pintype "passive"))
      (node (ref "C210") (pin "1") (pinfunction "1_1") (pintype "passive"))
      (node (ref "IC10") (pin "F11") (pinfunction "GND_F11") (pintype "power_in"))
      (node (ref "IC10") (pin "F6") (pinfunction "GND_F6") (pintype "power_in"))
      (node (ref "IC10") (pin "G10") (pinfunction "GND_G10") (pintype "power_in"))
      (node (ref "IC10") (pin "G7") (pinfunction "GND_G7") (pintype "power_in"))
      (node (ref "IC10") (pin "G8") (pinfunction "GND_G8") (pintype "power_in"))
      (node (ref "IC10") (pin "G9") (pinfunction "GND_G9") (pintype "power_in"))
      (node (ref "IC10") (pin "H10") (pinfunction "GND_H10") (pintype "power_in"))
      (node (ref "IC10") (pin "H7") (pinfunction "GND_H7") (pintype "power_in"))
      (node (ref "IC10") (pin "H8") (pinfunction "GND_H8") (pintype "power_in"))
      (node (ref "IC10") (pin "H9") (pinfunction "GND_H9") (pintype "power_in"))
      (node (ref "IC10") (pin "J10") (pinfunction "GND_J10") (pintype "power_in"))
      (node (ref "IC10") (pin "J7") (pinfunction "GND_J7") (pintype "power_in"))
      (node (ref "IC10") (pin "J8") (pinfunction "GND_J8") (pintype "power_in"))
      (node (ref "IC10") (pin "J9") (pinfunction "GND_J9") (pintype "power_in"))
      (node (ref "IC10") (pin "K10") (pinfunction "GND_K10") (pintype "power_in"))
      (node (ref "IC10") (pin "K7") (pinfunction "GND_K7") (pintype "power_in"))
      (node (ref "IC10") (pin "K8") (pinfunction "GND_K8") (pintype "power_in"))
      (node (ref "IC10") (pin "K9") (pinfunction "GND_K9") (pintype "power_in"))
      (node (ref "IC10") (pin "L11") (pinfunction "GND_L11") (pintype "power_in"))
      (node (ref "IC10") (pin "L6") (pinfunction "GND_L6") (pintype "power_in"))
      (node (ref "IC14") (pin "2") (pinfunction "GND_2") (pintype "power_in"))
      (node (ref "J8") (pin "1") (pinfunction "1_1") (pintype "bidirectional"))
      (node (ref "J8") (pin "11") (pinfunction "11_11") (pintype "bidirectional"))
      (node (ref "J8") (pin "13") (pinfunction "13_13") (pintype "bidirectional"))
      (node (ref "J8") (pin "3") (pinfunction "3_3") (pintype "bidirectional"))
      (node (ref "J8") (pin "5") (pinfunction "5_5") (pintype "bidirectional"))
      (node (ref "J8") (pin "7") (pinfunction "7_7") (pintype "bidirectional"))
      (node (ref "J8") (pin "9") (pinfunction "9_9") (pintype "bidirectional"))
      (node (ref "R111") (pin "1") (pinfunction "1_1") (pintype "passive"))
      (node (ref "R149") (pin "1") (pinfunction "1_1") (pintype "passive"))
      (node (ref "R172") (pin "1") (pinfunction "1_1") (pintype "passive"))
      (node (ref "R174") (pin "1") (pinfunction "1_1") (pintype "passive"))
      (node (ref "R83") (pin "1") (pinfunction "1_1") (pintype "passive"))
      (node (ref "R85") (pin "1") (pinfunction "1_1") (pintype "passive"))
      (node (ref "R86") (pin "1") (pinfunction "1_1") (pintype "passive"))
    )
    (net (code "176") (name "P1V8D") (class "Default")
      (node (ref "C152") (pin "2") (pinfunction "2_2") (pintype "passive"))
      (node (ref "C198") (pin "2") (pinfunction "2_2") (pintype "passive"))
      (node (ref "C199") (pin "2") (pinfunction "2_2") (pintype "passive"))
      (node (ref "C200") (pin "2") (pinfunction "2_2") (pintype "passive"))
      (node (ref "C201") (pin "2") (pinfunction "2_2") (pintype "passive"))
      (node (ref "IC10") (pin "D12") (pinfunction "VCC_D12") (pintype "power_in"))
      (node (ref "IC10") (pin "D5") (pinfunction "VCC_D5") (pintype "power_in"))
      (node (ref "IC10") (pin "K13") (pinfunction "VCC_K13") (pintype "power_in"))
      (node (ref "IC10") (pin "P3") (pinfunction "VCC_P3") (pintype "power_in"))
      (node (ref "IC14") (pin "5") (pinfunction "VOUT_5") (pintype "power_in"))
    )
    (net (code "177") (name "P3V3") (class "Default")
      (node (ref "C104") (pin "2") (pinfunction "2_2") (pintype "passive"))
      (node (ref "C175") (pin "2") (pinfunction "2_2") (pintype "passive"))
      (node (ref "C184") (pin "2") (pinfunction "2_2") (pintype "passive"))
      (node (ref "C185") (pin "2") (pinfunction "2_2") (pintype "passive"))
      (node (ref "C186") (pin "2") (pinfunction "2_2") (pintype "passive"))
      (node (ref "C187") (pin "2") (pinfunction "2_2") (pintype "passive"))
      (node (ref "C188") (pin "2") (pinfunction "2_2") (pintype "passive"))
      (node (ref "C192") (pin "2") (pinfunction "2_2") (pintype "passive"))
      (node (ref "C193") (pin "2") (pinfunction "2_2") (pintype "passive"))
      (node (ref "C197") (pin "2") (pinfunction "2_2") (pintype "passive"))
      (node (ref "C208") (pin "2") (pinfunction "2_2") (pintype "passive"))
      (node (ref "C209") (pin "2") (pinfunction "2_2") (pintype "passive"))
      (node (ref "C210") (pin "2") (pinfunction "2_2") (pintype "passive"))
      (node (ref "IC10") (pin "F10") (pinfunction "VCCIO2_F10") (pintype "power_in"))
      (node (ref "IC10") (pin "F4") (pinfunction "VAUX_F4") (pintype "power_in"))
      (node (ref "IC10") (pin "F7") (pinfunction "VCCIO2_F7") (pintype "power_in"))
      (node (ref "IC10") (pin "F8") (pinfunction "VCCIO2_F8") (pintype "power_in"))
      (node (ref "IC10") (pin "F9") (pinfunction "VCCIO2_F9") (pintype "power_in"))
      (node (ref "IC10") (pin "G6") (pinfunction "VCCIO2_G6") (pintype "power_in"))
      (node (ref "IC10") (pin "H11") (pinfunction "VCCIO2_H11") (pintype "power_in"))
      (node (ref "IC10") (pin "H6") (pinfunction "VCCIO2_H6") (pintype "power_in"))
      (node (ref "IC10") (pin "J11") (pinfunction "VCCIO1_J11") (pintype "power_in"))
      (node (ref "IC10") (pin "J6") (pinfunction "VCCIO1_J6") (pintype "power_in"))
      (node (ref "IC10") (pin "K11") (pinfunction "VCCIO1_K11") (pintype "power_in"))
      (node (ref "IC10") (pin "K6") (pinfunction "VCCIO1_K6") (pintype "power_in"))
      (node (ref "IC10") (pin "L10") (pinfunction "VCCIO1_L10") (pintype "power_in"))
      (node (ref "IC10") (pin "L7") (pinfunction "VCCIO1_L7") (pintype "power_in"))
      (node (ref "IC10") (pin "L8") (pinfunction "VCCIO1_L8") (pintype "power_in"))
      (node (ref "IC10") (pin "L9") (pinfunction "VCCIO1_L9") (pintype "power_in"))
      (node (ref "IC14") (pin "1") (pinfunction "VIN_1") (pintype "input"))
      (node (ref "IC14") (pin "3") (pinfunction "VEN_3") (pintype "input"))
      (node (ref "J8") (pin "2") (pinfunction "2_2") (pintype "bidirectional"))
      (node (ref "R1") (pin "1") (pinfunction "1_1") (pintype "passive"))
      (node (ref "R148") (pin "2") (pinfunction "2_2") (pintype "passive"))
      (node (ref "R171") (pin "1") (pinfunction "1_1") (pintype "passive"))
      (node (ref "R173") (pin "1") (pinfunction "1_1") (pintype "passive"))
      (node (ref "R175") (pin "1") (pinfunction "1_1") (pintype "passive"))
      (node (ref "R66") (pin "2") (pinfunction "2_2") (pintype "passive"))
      (node (ref "R67") (pin "2") (pinfunction "2_2") (pintype "passive"))
      (node (ref "SW1") (pin "1") (pinfunction "1_1") (pintype "passive"))
      (node (ref "SW1") (pin "2") (pinfunction "2_2") (pintype "passive"))
      (node (ref "SW1") (pin "3") (pinfunction "3_3") (pintype "passive"))
      (node (ref "SW1") (pin "4") (pinfunction "4_4") (pintype "passive"))
    )
    (net (code "178") (name "unconnected-(IC10A-I{slash}O-PadJ13)") (class "Default")
      (node (ref "IC10") (pin "J13") (pinfunction "I/O_J13") (pintype "bidirectional+no_connect"))
    )
    (net (code "179") (name "unconnected-(IC10A-I{slash}O-PadJ14)") (class "Default")
      (node (ref "IC10") (pin "J14") (pinfunction "I/O_J14") (pintype "bidirectional+no_connect"))
    )
    (net (code "180") (name "unconnected-(IC10A-I{slash}O-PadJ15)") (class "Default")
      (node (ref "IC10") (pin "J15") (pinfunction "I/O_J15") (pintype "bidirectional+no_connect"))
    )
    (net (code "181") (name "unconnected-(IC10A-I{slash}O-PadK14)") (class "Default")
      (node (ref "IC10") (pin "K14") (pinfunction "I/O_K14") (pintype "bidirectional"))
    )
    (net (code "182") (name "unconnected-(IC10A-I{slash}O-PadK16)") (class "Default")
      (node (ref "IC10") (pin "K16") (pinfunction "I/O_K16") (pintype "bidirectional+no_connect"))
    )
    (net (code "183") (name "unconnected-(IC10A-I{slash}O-PadL3)") (class "Default")
      (node (ref "IC10") (pin "L3") (pinfunction "I/O_L3") (pintype "bidirectional+no_connect"))
    )
    (net (code "184") (name "unconnected-(IC10A-I{slash}O-PadL12)") (class "Default")
      (node (ref "IC10") (pin "L12") (pinfunction "I/O_L12") (pintype "bidirectional+no_connect"))
    )
    (net (code "185") (name "unconnected-(IC10A-I{slash}O-PadL13)") (class "Default")
      (node (ref "IC10") (pin "L13") (pinfunction "I/O_L13") (pintype "bidirectional+no_connect"))
    )
    (net (code "186") (name "unconnected-(IC10A-I{slash}O-PadL14)") (class "Default")
      (node (ref "IC10") (pin "L14") (pinfunction "I/O_L14") (pintype "bidirectional+no_connect"))
    )
    (net (code "187") (name "unconnected-(IC10A-I{slash}O-PadM11)") (class "Default")
      (node (ref "IC10") (pin "M11") (pinfunction "I/O_M11") (pintype "bidirectional+no_connect"))
    )
    (net (code "188") (name "unconnected-(IC10A-I{slash}O-PadM12)") (class "Default")
      (node (ref "IC10") (pin "M12") (pinfunction "I/O_M12") (pintype "bidirectional+no_connect"))
    )
    (net (code "189") (name "unconnected-(IC10A-I{slash}O-PadM13)") (class "Default")
      (node (ref "IC10") (pin "M13") (pinfunction "I/O_M13") (pintype "bidirectional+no_connect"))
    )
    (net (code "190") (name "unconnected-(IC10A-I{slash}O-PadM14)") (class "Default")
      (node (ref "IC10") (pin "M14") (pinfunction "I/O_M14") (pintype "bidirectional"))
    )
    (net (code "191") (name "unconnected-(IC10A-I{slash}O-PadN8)") (class "Default")
      (node (ref "IC10") (pin "N8") (pinfunction "I/O_N8") (pintype "bidirectional+no_connect"))
    )
    (net (code "192") (name "unconnected-(IC10A-I{slash}O-PadN10)") (class "Default")
      (node (ref "IC10") (pin "N10") (pinfunction "I/O_N10") (pintype "bidirectional+no_connect"))
    )
    (net (code "193") (name "unconnected-(IC10A-I{slash}O-PadN11)") (class "Default")
      (node (ref "IC10") (pin "N11") (pinfunction "I/O_N11") (pintype "bidirectional+no_connect"))
    )
    (net (code "194") (name "unconnected-(IC10A-I{slash}O-PadP10)") (class "Default")
      (node (ref "IC10") (pin "P10") (pinfunction "I/O_P10") (pintype "bidirectional+no_connect"))
    )
    (net (code "195") (name "unconnected-(IC10A-I{slash}O-PadP13)") (class "Default")
      (node (ref "IC10") (pin "P13") (pinfunction "I/O_P13") (pintype "bidirectional+no_connect"))
    )
    (net (code "196") (name "unconnected-(IC10A-I{slash}O-PadP14)") (class "Default")
      (node (ref "IC10") (pin "P14") (pinfunction "I/O_P14") (pintype "bidirectional+no_connect"))
    )
    (net (code "197") (name "unconnected-(IC10A-I{slash}O-PadT6)") (class "Default")
      (node (ref "IC10") (pin "T6") (pinfunction "I/O_T6") (pintype "bidirectional+no_connect"))
    )
    (net (code "198") (name "unconnected-(IC10B-I{slash}O-PadB12)") (class "Default")
      (node (ref "IC10") (pin "B12") (pinfunction "I/O_B12") (pintype "bidirectional+no_connect"))
    )
    (net (code "199") (name "unconnected-(IC10B-I{slash}O-PadC1)") (class "Default")
      (node (ref "IC10") (pin "C1") (pinfunction "I/O_C1") (pintype "bidirectional+no_connect"))
    )
    (net (code "200") (name "unconnected-(IC10B-I{slash}O-PadE12)") (class "Default")
      (node (ref "IC10") (pin "E12") (pinfunction "I/O_E12") (pintype "bidirectional+no_connect"))
    )
    (net (code "201") (name "unconnected-(IC10B-I{slash}O-PadF3)") (class "Default")
      (node (ref "IC10") (pin "F3") (pinfunction "I/O_F3") (pintype "bidirectional+no_connect"))
    )
    (net (code "202") (name "unconnected-(IC10B-I{slash}O-PadF12)") (class "Default")
      (node (ref "IC10") (pin "F12") (pinfunction "I/O_F12") (pintype "bidirectional+no_connect"))
    )
    (net (code "203") (name "unconnected-(IC10B-I{slash}O-PadF13)") (class "Default")
      (node (ref "IC10") (pin "F13") (pinfunction "I/O_F13") (pintype "bidirectional+no_connect"))
    )
    (net (code "204") (name "unconnected-(IC10B-I{slash}O-PadF14)") (class "Default")
      (node (ref "IC10") (pin "F14") (pinfunction "I/O_F14") (pintype "bidirectional+no_connect"))
    )
    (net (code "205") (name "unconnected-(IC10B-I{slash}O-PadF15)") (class "Default")
      (node (ref "IC10") (pin "F15") (pinfunction "I/O_F15") (pintype "bidirectional+no_connect"))
    )
    (net (code "206") (name "unconnected-(IC10B-I{slash}O-PadG11)") (class "Default")
      (node (ref "IC10") (pin "G11") (pinfunction "I/O_G11") (pintype "bidirectional+no_connect"))
    )
    (net (code "207") (name "unconnected-(IC10B-I{slash}O-PadG13)") (class "Default")
      (node (ref "IC10") (pin "G13") (pinfunction "I/O_G13") (pintype "bidirectional+no_connect"))
    )
    (net (code "208") (name "unconnected-(IC10B-I{slash}O-PadG14)") (class "Default")
      (node (ref "IC10") (pin "G14") (pinfunction "I/O_G14") (pintype "bidirectional+no_connect"))
    )
    (net (code "209") (name "unconnected-(IC10B-I{slash}O-PadG15)") (class "Default")
      (node (ref "IC10") (pin "G15") (pinfunction "I/O_G15") (pintype "bidirectional+no_connect"))
    )
    (net (code "210") (name "unconnected-(IC10B-I{slash}O-PadG16)") (class "Default")
      (node (ref "IC10") (pin "G16") (pinfunction "I/O_G16") (pintype "bidirectional+no_connect"))
    )
    (net (code "211") (name "unconnected-(IC10B-I{slash}O-PadH12)") (class "Default")
      (node (ref "IC10") (pin "H12") (pinfunction "I/O_H12") (pintype "bidirectional+no_connect"))
    )
    (net (code "212") (name "unconnected-(IC10B-I{slash}O-PadH13)") (class "Default")
      (node (ref "IC10") (pin "H13") (pinfunction "I/O_H13") (pintype "bidirectional+no_connect"))
    )
    (net (code "213") (name "unconnected-(IC10B-I{slash}O-PadH14)") (class "Default")
      (node (ref "IC10") (pin "H14") (pinfunction "I/O_H14") (pintype "bidirectional+no_connect"))
    )
    (net (code "214") (name "unconnected-(IC10B-I{slash}O-PadH15)") (class "Default")
      (node (ref "IC10") (pin "H15") (pinfunction "I/O_H15") (pintype "bidirectional+no_connect"))
    )
    (net (code "215") (name "unconnected-(IC10B-I{slash}O-PadH16)") (class "Default")
      (node (ref "IC10") (pin "H16") (pinfunction "I/O_H16") (pintype "bidirectional+no_connect"))
    )
    (net (code "216") (name "unconnected-(IC10B-I{slash}O-PadJ12)") (class "Default")
      (node (ref "IC10") (pin "J12") (pinfunction "I/O_J12") (pintype "bidirectional+no_connect"))
    )
    (net (code "217") (name "unconnected-(IC10F-NC-PadA1)") (class "Default")
      (node (ref "IC10") (pin "A1") (pinfunction "NC_A1") (pintype "passive+no_connect"))
    )
    (net (code "218") (name "unconnected-(IC10F-NC-PadC2)") (class "Default")
      (node (ref "IC10") (pin "C2") (pinfunction "NC_C2") (pintype "passive+no_connect"))
    )
    (net (code "219") (name "unconnected-(IC10F-NC-PadC5)") (class "Default")
      (node (ref "IC10") (pin "C5") (pinfunction "NC_C5") (pintype "passive+no_connect"))
    )
    (net (code "220") (name "unconnected-(IC10F-NC-PadC6)") (class "Default")
      (node (ref "IC10") (pin "C6") (pinfunction "NC_C6") (pintype "passive+no_connect"))
    )
    (net (code "221") (name "unconnected-(IC10F-NC-PadC15)") (class "Default")
      (node (ref "IC10") (pin "C15") (pinfunction "NC_C15") (pintype "passive+no_connect"))
    )
    (net (code "222") (name "unconnected-(IC10F-NC-PadD1)") (class "Default")
      (node (ref "IC10") (pin "D1") (pinfunction "NC_D1") (pintype "passive+no_connect"))
    )
    (net (code "223") (name "unconnected-(IC10F-NC-PadD6)") (class "Default")
      (node (ref "IC10") (pin "D6") (pinfunction "NC_D6") (pintype "passive+no_connect"))
    )
    (net (code "224") (name "unconnected-(IC10F-NC-PadD14)") (class "Default")
      (node (ref "IC10") (pin "D14") (pinfunction "NC_D14") (pintype "passive+no_connect"))
    )
    (net (code "225") (name "unconnected-(IC10F-NC-PadD16)") (class "Default")
      (node (ref "IC10") (pin "D16") (pinfunction "NC_D16") (pintype "passive+no_connect"))
    )
    (net (code "226") (name "unconnected-(IC10F-NC-PadE1)") (class "Default")
      (node (ref "IC10") (pin "E1") (pinfunction "NC_E1") (pintype "passive+no_connect"))
    )
    (net (code "227") (name "unconnected-(IC10F-NC-PadE6)") (class "Default")
      (node (ref "IC10") (pin "E6") (pinfunction "NC_E6") (pintype "passive+no_connect"))
    )
    (net (code "228") (name "unconnected-(IC10F-NC-PadE7)") (class "Default")
      (node (ref "IC10") (pin "E7") (pinfunction "NC_E7") (pintype "passive+no_connect"))
    )
    (net (code "229") (name "unconnected-(IC10F-NC-PadF1)") (class "Default")
      (node (ref "IC10") (pin "F1") (pinfunction "NC_F1") (pintype "passive+no_connect"))
    )
    (net (code "230") (name "unconnected-(IC10F-NC-PadG1)") (class "Default")
      (node (ref "IC10") (pin "G1") (pinfunction "NC_G1") (pintype "passive+no_connect"))
    )
    (net (code "231") (name "unconnected-(IC10F-NC-PadG2)") (class "Default")
      (node (ref "IC10") (pin "G2") (pinfunction "NC_G2") (pintype "passive+no_connect"))
    )
    (net (code "232") (name "unconnected-(IC10F-NC-PadG12)") (class "Default")
      (node (ref "IC10") (pin "G12") (pinfunction "NC_G12") (pintype "passive+no_connect"))
    )
    (net (code "233") (name "unconnected-(IC10F-NC-PadJ16)") (class "Default")
      (node (ref "IC10") (pin "J16") (pinfunction "NC_J16") (pintype "passive+no_connect"))
    )
    (net (code "234") (name "unconnected-(IC10F-NC-PadK12)") (class "Default")
      (node (ref "IC10") (pin "K12") (pinfunction "NC_K12") (pintype "passive+no_connect"))
    )
    (net (code "235") (name "unconnected-(IC10F-NC-PadM4)") (class "Default")
      (node (ref "IC10") (pin "M4") (pinfunction "NC_M4") (pintype "passive+no_connect"))
    )
    (net (code "236") (name "unconnected-(IC10F-NC-PadM9)") (class "Default")
      (node (ref "IC10") (pin "M9") (pinfunction "NC_M9") (pintype "passive+no_connect"))
    )
    (net (code "237") (name "unconnected-(IC10F-NC-PadM10)") (class "Default")
      (node (ref "IC10") (pin "M10") (pinfunction "NC_M10") (pintype "passive+no_connect"))
    )
    (net (code "238") (name "unconnected-(IC10F-NC-PadP9)") (class "Default")
      (node (ref "IC10") (pin "P9") (pinfunction "NC_P9") (pintype "passive+no_connect"))
    )
    (net (code "239") (name "unconnected-(IC10F-NC-PadP11)") (class "Default")
      (node (ref "IC10") (pin "P11") (pinfunction "NC_P11") (pintype "passive+no_connect"))
    )
    (net (code "240") (name "unconnected-(IC10F-NC-PadT9)") (class "Default")
      (node (ref "IC10") (pin "T9") (pinfunction "NC_T9") (pintype "passive+no_connect"))
    )
    (net (code "241") (name "unconnected-(IC10F-NC-PadT11)") (class "Default")
      (node (ref "IC10") (pin "T11") (pinfunction "NC_T11") (pintype "passive+no_connect"))
    )
    (net (code "242") (name "unconnected-(IC10F-NC-PadT12)") (class "Default")
      (node (ref "IC10") (pin "T12") (pinfunction "NC_T12") (pintype "passive+no_connect"))
    )
    (net (code "243") (name "unconnected-(IC10F-NC-PadT13)") (class "Default")
      (node (ref "IC10") (pin "T13") (pinfunction "NC_T13") (pintype "passive+no_connect"))
    )
    (net (code "244") (name "unconnected-(IC10F-NC-PadT14)") (class "Default")
      (node (ref "IC10") (pin "T14") (pinfunction "NC_T14") (pintype "passive+no_connect"))
    )
    (net (code "245") (name "unconnected-(IC14-NC-Pad4)") (class "Default")
      (node (ref "IC14") (pin "4") (pinfunction "NC_4") (pintype "passive+no_connect"))
    )
    (net (code "246") (name "unconnected-(J8-Pad12)") (class "Default")
      (node (ref "J8") (pin "12") (pinfunction "12_12") (pintype "bidirectional+no_connect"))
    )
    (net (code "247") (name "unconnected-(J8-Pad14)") (class "Default")
      (node (ref "J8") (pin "14") (pinfunction "14_14") (pintype "bidirectional+no_connect"))
    )
  )
)
